# fscv8ch.net
KiCad netlist of a schematic drawn in Altium Designer
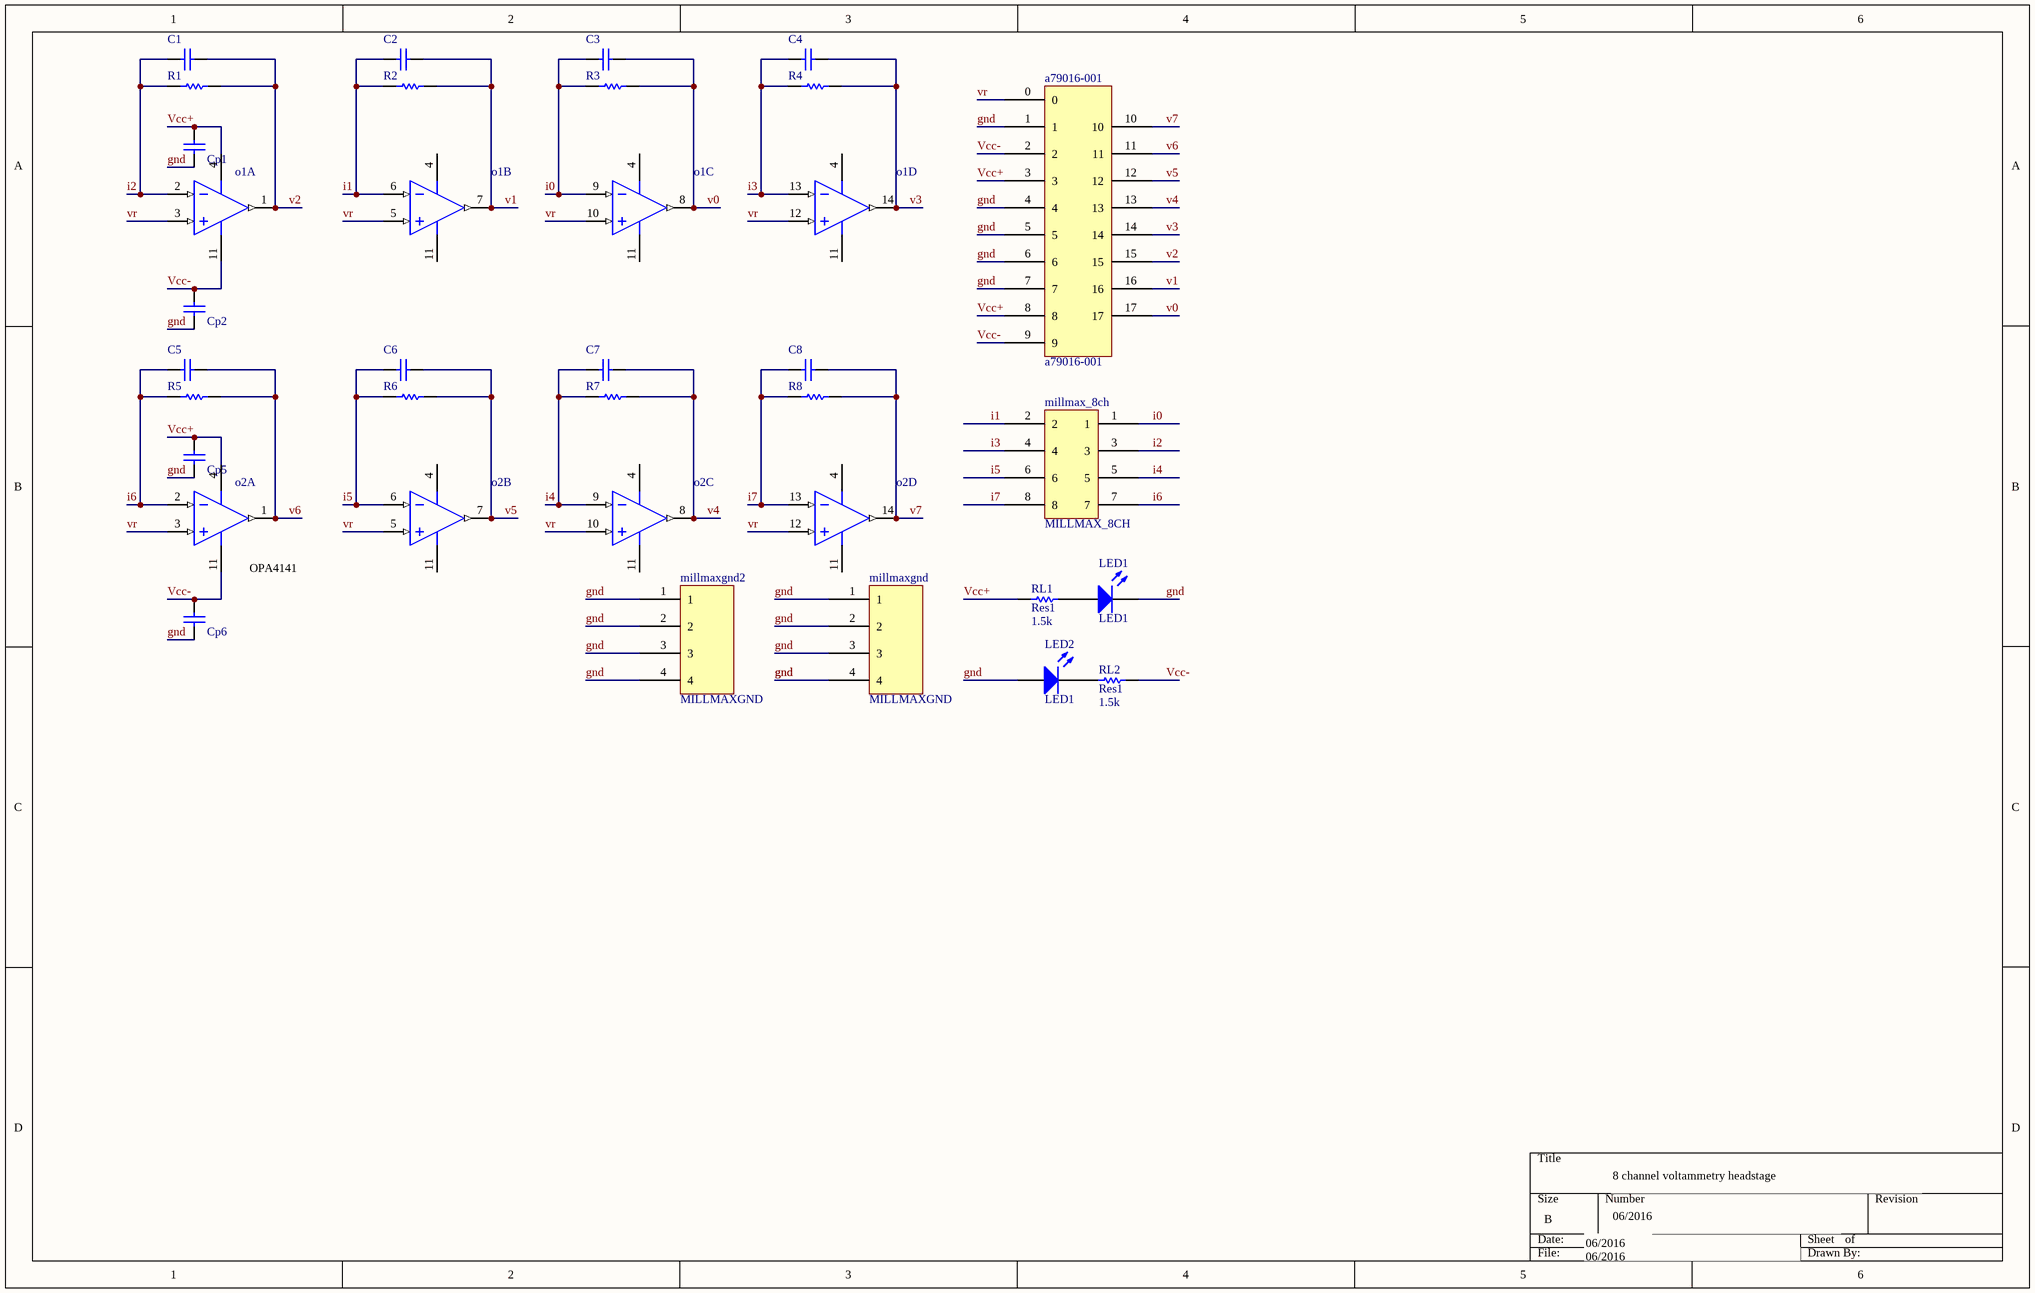
[diagram p0: fscv8ch.SCHDOC]

(export (version "E")
  (design (tool "Eeschema 10.0.6"))
  (components
    (comp (ref "a79016-001")
      (value "~")
      (footprint "A79016-001_finalnovias")
      (libsource (lib "connectors") (part "a79016-001"))
    )
    (comp (ref "C1")
      (value "Cap")
      (footprint "0402")
      (description "Capacitor")
      (fields (field (name "MANUFACTURER") "Generic Components") (field (name "PUBLISHER") "Altium Limited"))
      (libsource (lib "Miscellaneous Devices") (part "Cap"))
    )
    (comp (ref "C2")
      (value "Cap")
      (footprint "0402")
      (description "Capacitor")
      (fields (field (name "MANUFACTURER") "Generic Components") (field (name "PUBLISHER") "Altium Limited"))
      (libsource (lib "Miscellaneous Devices") (part "Cap"))
    )
    (comp (ref "C3")
      (value "Cap")
      (footprint "0402")
      (description "Capacitor")
      (fields (field (name "MANUFACTURER") "Generic Components") (field (name "PUBLISHER") "Altium Limited"))
      (libsource (lib "Miscellaneous Devices") (part "Cap"))
    )
    (comp (ref "C4")
      (value "Cap")
      (footprint "0402")
      (description "Capacitor")
      (fields (field (name "MANUFACTURER") "Generic Components") (field (name "PUBLISHER") "Altium Limited"))
      (libsource (lib "Miscellaneous Devices") (part "Cap"))
    )
    (comp (ref "C5")
      (value "Cap")
      (footprint "0402")
      (description "Capacitor")
      (fields (field (name "MANUFACTURER") "Generic Components") (field (name "PUBLISHER") "Altium Limited"))
      (libsource (lib "Miscellaneous Devices") (part "Cap"))
    )
    (comp (ref "C6")
      (value "Cap")
      (footprint "0402")
      (description "Capacitor")
      (fields (field (name "MANUFACTURER") "Generic Components") (field (name "PUBLISHER") "Altium Limited"))
      (libsource (lib "Miscellaneous Devices") (part "Cap"))
    )
    (comp (ref "C7")
      (value "Cap")
      (footprint "0402")
      (description "Capacitor")
      (fields (field (name "MANUFACTURER") "Generic Components") (field (name "PUBLISHER") "Altium Limited"))
      (libsource (lib "Miscellaneous Devices") (part "Cap"))
    )
    (comp (ref "C8")
      (value "Cap")
      (footprint "0402")
      (description "Capacitor")
      (fields (field (name "MANUFACTURER") "Generic Components") (field (name "PUBLISHER") "Altium Limited"))
      (libsource (lib "Miscellaneous Devices") (part "Cap"))
    )
    (comp (ref "Cp1")
      (value "Cap")
      (footprint "0402")
      (description "Capacitor")
      (fields (field (name "MANUFACTURER") "Generic Components") (field (name "PUBLISHER") "Altium Limited"))
      (libsource (lib "Miscellaneous Devices") (part "Cap"))
    )
    (comp (ref "Cp2")
      (value "Cap")
      (footprint "0402")
      (description "Capacitor")
      (fields (field (name "MANUFACTURER") "Generic Components") (field (name "PUBLISHER") "Altium Limited"))
      (libsource (lib "Miscellaneous Devices") (part "Cap"))
    )
    (comp (ref "Cp5")
      (value "Cap")
      (footprint "0402")
      (description "Capacitor")
      (fields (field (name "MANUFACTURER") "Generic Components") (field (name "PUBLISHER") "Altium Limited"))
      (libsource (lib "Miscellaneous Devices") (part "Cap"))
    )
    (comp (ref "Cp6")
      (value "Cap")
      (footprint "0402")
      (description "Capacitor")
      (fields (field (name "MANUFACTURER") "Generic Components") (field (name "PUBLISHER") "Altium Limited"))
      (libsource (lib "Miscellaneous Devices") (part "Cap"))
    )
    (comp (ref "LED1")
      (value "LED1")
      (footprint "LED_smd")
      (description "Typical RED GaAs LED")
      (fields (field (name "MANUFACTURER") "Generic Components") (field (name "PUBLISHER") "Altium Limited"))
      (libsource (lib "Miscellaneous Devices") (part "LED1"))
    )
    (comp (ref "LED2")
      (value "LED1")
      (footprint "LED_smd")
      (description "Typical RED GaAs LED")
      (fields (field (name "MANUFACTURER") "Generic Components") (field (name "PUBLISHER") "Altium Limited"))
      (libsource (lib "Miscellaneous Devices") (part "LED1"))
    )
    (comp (ref "millmaxgnd")
      (value "MILLMAXGND")
      (footprint "millmax833-43-008-20-001000gnd")
      (libsource (lib "connectors") (part "MILLMAXGND"))
    )
    (comp (ref "millmaxgnd2")
      (value "MILLMAXGND")
      (footprint "millmax833-43-008-20-001000gnd")
      (libsource (lib "connectors") (part "MILLMAXGND"))
    )
    (comp (ref "millmax_8ch")
      (value "MILLMAX_8CH")
      (footprint "millmax833-d -8ch")
      (libsource (lib "connectors") (part "MILLMAX_8CH"))
    )
    (comp (ref "o1")
      (value "TLC274ACD")
      (footprint "SO-G14")
      (description "LinCMOS Precision Quad Operational Amplifier")
      (fields (field (name "MANUFACTURER") "Texas Instruments") (field (name "PUBLISHER") "Altium Limited"))
      (libsource (lib "TI Operational Amplifier") (part "TLC274ACD"))
    )
    (comp (ref "o2")
      (value "TLC274ACD")
      (footprint "SO-G14")
      (description "LinCMOS Precision Quad Operational Amplifier")
      (fields (field (name "MANUFACTURER") "Texas Instruments") (field (name "PUBLISHER") "Altium Limited"))
      (libsource (lib "TI Operational Amplifier") (part "TLC274ACD"))
    )
    (comp (ref "R1")
      (value "Res Semi")
      (footprint "0402")
      (description "Semiconductor Resistor")
      (fields (field (name "MANUFACTURER") "Generic Components") (field (name "PUBLISHER") "Altium Limited"))
      (libsource (lib "Miscellaneous Devices") (part "Res Semi"))
    )
    (comp (ref "R2")
      (value "Res Semi")
      (footprint "0402")
      (description "Semiconductor Resistor")
      (fields (field (name "MANUFACTURER") "Generic Components") (field (name "PUBLISHER") "Altium Limited"))
      (libsource (lib "Miscellaneous Devices") (part "Res Semi"))
    )
    (comp (ref "R3")
      (value "Res Semi")
      (footprint "0402")
      (description "Semiconductor Resistor")
      (fields (field (name "MANUFACTURER") "Generic Components") (field (name "PUBLISHER") "Altium Limited"))
      (libsource (lib "Miscellaneous Devices") (part "Res Semi"))
    )
    (comp (ref "R4")
      (value "Res Semi")
      (footprint "0402")
      (description "Semiconductor Resistor")
      (fields (field (name "MANUFACTURER") "Generic Components") (field (name "PUBLISHER") "Altium Limited"))
      (libsource (lib "Miscellaneous Devices") (part "Res Semi"))
    )
    (comp (ref "R5")
      (value "Res Semi")
      (footprint "0402")
      (description "Semiconductor Resistor")
      (fields (field (name "MANUFACTURER") "Generic Components") (field (name "PUBLISHER") "Altium Limited"))
      (libsource (lib "Miscellaneous Devices") (part "Res Semi"))
    )
    (comp (ref "R6")
      (value "Res Semi")
      (footprint "0402")
      (description "Semiconductor Resistor")
      (fields (field (name "MANUFACTURER") "Generic Components") (field (name "PUBLISHER") "Altium Limited"))
      (libsource (lib "Miscellaneous Devices") (part "Res Semi"))
    )
    (comp (ref "R7")
      (value "Res Semi")
      (footprint "0402")
      (description "Semiconductor Resistor")
      (fields (field (name "MANUFACTURER") "Generic Components") (field (name "PUBLISHER") "Altium Limited"))
      (libsource (lib "Miscellaneous Devices") (part "Res Semi"))
    )
    (comp (ref "R8")
      (value "Res Semi")
      (footprint "0402")
      (description "Semiconductor Resistor")
      (fields (field (name "MANUFACTURER") "Generic Components") (field (name "PUBLISHER") "Altium Limited"))
      (libsource (lib "Miscellaneous Devices") (part "Res Semi"))
    )
    (comp (ref "RL1")
      (value "Res1")
      (footprint "0402")
      (description "Resistor")
      (fields
        (field (name "MANUFACTURER") "Generic Components")
        (field (name "ALTIUM_VALUE") "1.5k")
        (field (name "PUBLISHER") "Altium Limited")
      )
      (libsource (lib "Miscellaneous Devices") (part "Res1"))
    )
    (comp (ref "RL2")
      (value "Res1")
      (footprint "0402")
      (description "Resistor")
      (fields
        (field (name "MANUFACTURER") "Generic Components")
        (field (name "ALTIUM_VALUE") "1.5k")
        (field (name "PUBLISHER") "Altium Limited")
      )
      (libsource (lib "Miscellaneous Devices") (part "Res1"))
    )
  )
  (nets
    (net (code "1") (name "/Vcc+") (class "Default")
      (node (ref "Cp1") (pin "2") (pinfunction "2_2") (pintype "passive"))
      (node (ref "Cp5") (pin "2") (pinfunction "2_2") (pintype "passive"))
      (node (ref "RL1") (pin "2") (pinfunction "2_2") (pintype "passive"))
      (node (ref "a79016-001") (pin "3") (pinfunction "3_3") (pintype "passive"))
      (node (ref "a79016-001") (pin "8") (pinfunction "8_8") (pintype "passive"))
      (node (ref "o1") (pin "4") (pinfunction "V+_4") (pintype "power_in"))
      (node (ref "o2") (pin "4") (pinfunction "V+_4") (pintype "power_in"))
    )
    (net (code "2") (name "/Vcc-") (class "Default")
      (node (ref "Cp2") (pin "2") (pinfunction "2_2") (pintype "passive"))
      (node (ref "Cp6") (pin "2") (pinfunction "2_2") (pintype "passive"))
      (node (ref "RL2") (pin "1") (pinfunction "1_1") (pintype "passive"))
      (node (ref "a79016-001") (pin "2") (pinfunction "2_2") (pintype "passive"))
      (node (ref "a79016-001") (pin "9") (pinfunction "9_9") (pintype "passive"))
      (node (ref "o1") (pin "11") (pinfunction "V-_11") (pintype "power_in"))
      (node (ref "o2") (pin "11") (pinfunction "V-_11") (pintype "power_in"))
    )
    (net (code "3") (name "/gnd") (class "Default")
      (node (ref "Cp1") (pin "1") (pinfunction "1_1") (pintype "passive"))
      (node (ref "Cp2") (pin "1") (pinfunction "1_1") (pintype "passive"))
      (node (ref "Cp5") (pin "1") (pinfunction "1_1") (pintype "passive"))
      (node (ref "Cp6") (pin "1") (pinfunction "1_1") (pintype "passive"))
      (node (ref "LED1") (pin "2") (pinfunction "K_2") (pintype "passive"))
      (node (ref "LED2") (pin "1") (pinfunction "A_1") (pintype "passive"))
      (node (ref "a79016-001") (pin "1") (pinfunction "1_1") (pintype "passive"))
      (node (ref "a79016-001") (pin "4") (pinfunction "4_4") (pintype "passive"))
      (node (ref "a79016-001") (pin "5") (pinfunction "5_5") (pintype "passive"))
      (node (ref "a79016-001") (pin "6") (pinfunction "6_6") (pintype "passive"))
      (node (ref "a79016-001") (pin "7") (pinfunction "7_7") (pintype "passive"))
      (node (ref "millmaxgnd") (pin "1") (pinfunction "1_1") (pintype "passive"))
      (node (ref "millmaxgnd") (pin "2") (pinfunction "2_2") (pintype "passive"))
      (node (ref "millmaxgnd") (pin "3") (pinfunction "3_3") (pintype "passive"))
      (node (ref "millmaxgnd") (pin "4") (pinfunction "4_4") (pintype "passive"))
      (node (ref "millmaxgnd2") (pin "1") (pinfunction "1_1") (pintype "passive"))
      (node (ref "millmaxgnd2") (pin "2") (pinfunction "2_2") (pintype "passive"))
      (node (ref "millmaxgnd2") (pin "3") (pinfunction "3_3") (pintype "passive"))
      (node (ref "millmaxgnd2") (pin "4") (pinfunction "4_4") (pintype "passive"))
    )
    (net (code "4") (name "/i0") (class "Default")
      (node (ref "C3") (pin "1") (pinfunction "1_1") (pintype "passive"))
      (node (ref "R3") (pin "1") (pinfunction "1_1") (pintype "passive"))
      (node (ref "millmax_8ch") (pin "1") (pinfunction "1_1") (pintype "passive"))
      (node (ref "o1") (pin "9") (pinfunction "IN-_9") (pintype "input"))
    )
    (net (code "5") (name "/i1") (class "Default")
      (node (ref "C2") (pin "1") (pinfunction "1_1") (pintype "passive"))
      (node (ref "R2") (pin "1") (pinfunction "1_1") (pintype "passive"))
      (node (ref "millmax_8ch") (pin "2") (pinfunction "2_2") (pintype "passive"))
      (node (ref "o1") (pin "6") (pinfunction "IN-_6") (pintype "input"))
    )
    (net (code "6") (name "/i2") (class "Default")
      (node (ref "C1") (pin "1") (pinfunction "1_1") (pintype "passive"))
      (node (ref "R1") (pin "1") (pinfunction "1_1") (pintype "passive"))
      (node (ref "millmax_8ch") (pin "3") (pinfunction "3_3") (pintype "passive"))
      (node (ref "o1") (pin "2") (pinfunction "IN-_2") (pintype "input"))
    )
    (net (code "7") (name "/i3") (class "Default")
      (node (ref "C4") (pin "1") (pinfunction "1_1") (pintype "passive"))
      (node (ref "R4") (pin "1") (pinfunction "1_1") (pintype "passive"))
      (node (ref "millmax_8ch") (pin "4") (pinfunction "4_4") (pintype "passive"))
      (node (ref "o1") (pin "13") (pinfunction "IN-_13") (pintype "input"))
    )
    (net (code "8") (name "/i4") (class "Default")
      (node (ref "C7") (pin "1") (pinfunction "1_1") (pintype "passive"))
      (node (ref "R7") (pin "1") (pinfunction "1_1") (pintype "passive"))
      (node (ref "millmax_8ch") (pin "5") (pinfunction "5_5") (pintype "passive"))
      (node (ref "o2") (pin "9") (pinfunction "IN-_9") (pintype "input"))
    )
    (net (code "9") (name "/i5") (class "Default")
      (node (ref "C6") (pin "1") (pinfunction "1_1") (pintype "passive"))
      (node (ref "R6") (pin "1") (pinfunction "1_1") (pintype "passive"))
      (node (ref "millmax_8ch") (pin "6") (pinfunction "6_6") (pintype "passive"))
      (node (ref "o2") (pin "6") (pinfunction "IN-_6") (pintype "input"))
    )
    (net (code "10") (name "/i6") (class "Default")
      (node (ref "C5") (pin "1") (pinfunction "1_1") (pintype "passive"))
      (node (ref "R5") (pin "1") (pinfunction "1_1") (pintype "passive"))
      (node (ref "millmax_8ch") (pin "7") (pinfunction "7_7") (pintype "passive"))
      (node (ref "o2") (pin "2") (pinfunction "IN-_2") (pintype "input"))
    )
    (net (code "11") (name "/i7") (class "Default")
      (node (ref "C8") (pin "1") (pinfunction "1_1") (pintype "passive"))
      (node (ref "R8") (pin "1") (pinfunction "1_1") (pintype "passive"))
      (node (ref "millmax_8ch") (pin "8") (pinfunction "8_8") (pintype "passive"))
      (node (ref "o2") (pin "13") (pinfunction "IN-_13") (pintype "input"))
    )
    (net (code "12") (name "/v0") (class "Default")
      (node (ref "C3") (pin "2") (pinfunction "2_2") (pintype "passive"))
      (node (ref "R3") (pin "2") (pinfunction "2_2") (pintype "passive"))
      (node (ref "a79016-001") (pin "17") (pinfunction "17_17") (pintype "passive"))
      (node (ref "o1") (pin "8") (pinfunction "OUT_8") (pintype "output"))
    )
    (net (code "13") (name "/v1") (class "Default")
      (node (ref "C2") (pin "2") (pinfunction "2_2") (pintype "passive"))
      (node (ref "R2") (pin "2") (pinfunction "2_2") (pintype "passive"))
      (node (ref "a79016-001") (pin "16") (pinfunction "16_16") (pintype "passive"))
      (node (ref "o1") (pin "7") (pinfunction "OUT_7") (pintype "output"))
    )
    (net (code "14") (name "/v2") (class "Default")
      (node (ref "C1") (pin "2") (pinfunction "2_2") (pintype "passive"))
      (node (ref "R1") (pin "2") (pinfunction "2_2") (pintype "passive"))
      (node (ref "a79016-001") (pin "15") (pinfunction "15_15") (pintype "passive"))
      (node (ref "o1") (pin "1") (pinfunction "OUT_1") (pintype "output"))
    )
    (net (code "15") (name "/v3") (class "Default")
      (node (ref "C4") (pin "2") (pinfunction "2_2") (pintype "passive"))
      (node (ref "R4") (pin "2") (pinfunction "2_2") (pintype "passive"))
      (node (ref "a79016-001") (pin "14") (pinfunction "14_14") (pintype "passive"))
      (node (ref "o1") (pin "14") (pinfunction "OUT_14") (pintype "output"))
    )
    (net (code "16") (name "/v4") (class "Default")
      (node (ref "C7") (pin "2") (pinfunction "2_2") (pintype "passive"))
      (node (ref "R7") (pin "2") (pinfunction "2_2") (pintype "passive"))
      (node (ref "a79016-001") (pin "13") (pinfunction "13_13") (pintype "passive"))
      (node (ref "o2") (pin "8") (pinfunction "OUT_8") (pintype "output"))
    )
    (net (code "17") (name "/v5") (class "Default")
      (node (ref "C6") (pin "2") (pinfunction "2_2") (pintype "passive"))
      (node (ref "R6") (pin "2") (pinfunction "2_2") (pintype "passive"))
      (node (ref "a79016-001") (pin "12") (pinfunction "12_12") (pintype "passive"))
      (node (ref "o2") (pin "7") (pinfunction "OUT_7") (pintype "output"))
    )
    (net (code "18") (name "/v6") (class "Default")
      (node (ref "C5") (pin "2") (pinfunction "2_2") (pintype "passive"))
      (node (ref "R5") (pin "2") (pinfunction "2_2") (pintype "passive"))
      (node (ref "a79016-001") (pin "11") (pinfunction "11_11") (pintype "passive"))
      (node (ref "o2") (pin "1") (pinfunction "OUT_1") (pintype "output"))
    )
    (net (code "19") (name "/v7") (class "Default")
      (node (ref "C8") (pin "2") (pinfunction "2_2") (pintype "passive"))
      (node (ref "R8") (pin "2") (pinfunction "2_2") (pintype "passive"))
      (node (ref "a79016-001") (pin "10") (pinfunction "10_10") (pintype "passive"))
      (node (ref "o2") (pin "14") (pinfunction "OUT_14") (pintype "output"))
    )
    (net (code "20") (name "/vr") (class "Default")
      (node (ref "a79016-001") (pin "0") (pinfunction "0_0") (pintype "passive"))
      (node (ref "o1") (pin "10") (pinfunction "IN+_10") (pintype "input"))
      (node (ref "o1") (pin "12") (pinfunction "IN+_12") (pintype "input"))
      (node (ref "o1") (pin "3") (pinfunction "IN+_3") (pintype "input"))
      (node (ref "o1") (pin "5") (pinfunction "IN+_5") (pintype "input"))
      (node (ref "o2") (pin "10") (pinfunction "IN+_10") (pintype "input"))
      (node (ref "o2") (pin "12") (pinfunction "IN+_12") (pintype "input"))
      (node (ref "o2") (pin "3") (pinfunction "IN+_3") (pintype "input"))
      (node (ref "o2") (pin "5") (pinfunction "IN+_5") (pintype "input"))
    )
    (net (code "21") (name "Net-(LED1-A)") (class "Default")
      (node (ref "LED1") (pin "1") (pinfunction "A_1") (pintype "passive"))
      (node (ref "RL1") (pin "1") (pinfunction "1_1") (pintype "passive"))
    )
    (net (code "22") (name "Net-(LED2-K)") (class "Default")
      (node (ref "LED2") (pin "2") (pinfunction "K_2") (pintype "passive"))
      (node (ref "RL2") (pin "2") (pinfunction "2_2") (pintype "passive"))
    )
    (net (code "23") (name "unconnected-(o1B-V+-Pad4)") (class "Default")
      (node (ref "o1") (pin "4") (pinfunction "V+_4") (pintype "power_in"))
    )
    (net (code "24") (name "unconnected-(o1B-V--Pad11)") (class "Default")
      (node (ref "o1") (pin "11") (pinfunction "V-_11") (pintype "power_in"))
    )
    (net (code "25") (name "unconnected-(o1C-V+-Pad4)") (class "Default")
      (node (ref "o1") (pin "4") (pinfunction "V+_4") (pintype "power_in"))
    )
    (net (code "26") (name "unconnected-(o1C-V--Pad11)") (class "Default")
      (node (ref "o1") (pin "11") (pinfunction "V-_11") (pintype "power_in"))
    )
    (net (code "27") (name "unconnected-(o1D-V+-Pad4)") (class "Default")
      (node (ref "o1") (pin "4") (pinfunction "V+_4") (pintype "power_in"))
    )
    (net (code "28") (name "unconnected-(o1D-V--Pad11)") (class "Default")
      (node (ref "o1") (pin "11") (pinfunction "V-_11") (pintype "power_in"))
    )
    (net (code "29") (name "unconnected-(o2B-V+-Pad4)") (class "Default")
      (node (ref "o2") (pin "4") (pinfunction "V+_4") (pintype "power_in"))
    )
    (net (code "30") (name "unconnected-(o2B-V--Pad11)") (class "Default")
      (node (ref "o2") (pin "11") (pinfunction "V-_11") (pintype "power_in"))
    )
    (net (code "31") (name "unconnected-(o2C-V+-Pad4)") (class "Default")
      (node (ref "o2") (pin "4") (pinfunction "V+_4") (pintype "power_in"))
    )
    (net (code "32") (name "unconnected-(o2C-V--Pad11)") (class "Default")
      (node (ref "o2") (pin "11") (pinfunction "V-_11") (pintype "power_in"))
    )
    (net (code "33") (name "unconnected-(o2D-V+-Pad4)") (class "Default")
      (node (ref "o2") (pin "4") (pinfunction "V+_4") (pintype "power_in"))
    )
    (net (code "34") (name "unconnected-(o2D-V--Pad11)") (class "Default")
      (node (ref "o2") (pin "11") (pinfunction "V-_11") (pintype "power_in"))
    )
  )
)
